# DSP1.net
KiCad netlist of a schematic drawn in Altium Designer
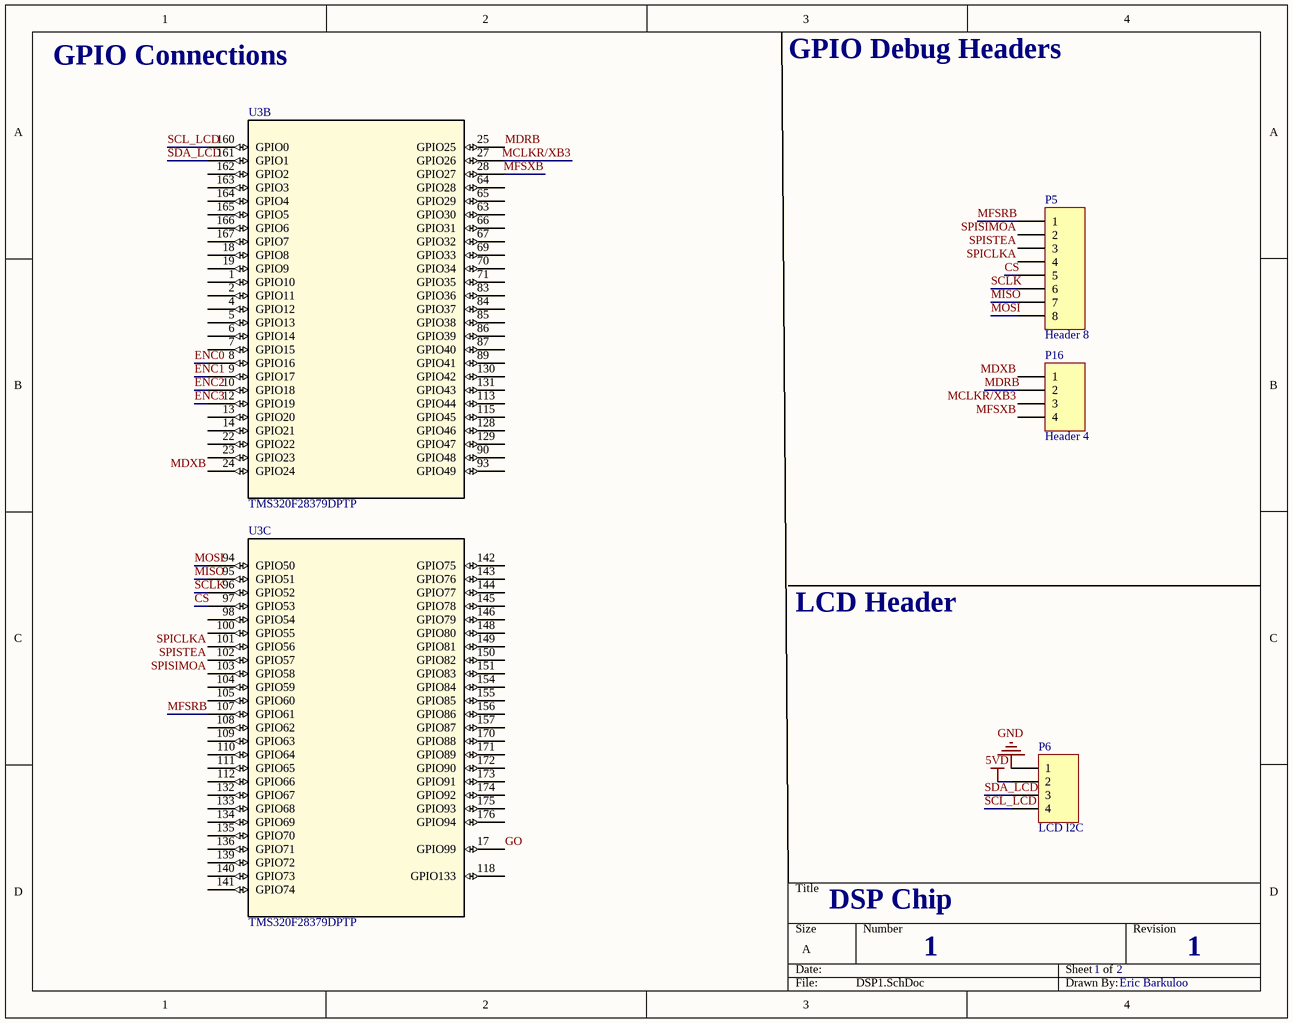
[diagram p0: DSP1.SchDoc]

(export (version "E")
  (design (tool "Eeschema 10.0.6"))
  (components
    (comp (ref "P5")
      (value "Header 8")
      (footprint "HDR1X8")
      (description "Header, 8-Pin")
      (fields (field (name "PUBLISHER") "Altium Limited"))
      (libsource (lib "Miscellaneous Connectors") (part "Header 8"))
    )
    (comp (ref "P6")
      (value "LCD I2C")
      (footprint "HDR1X4")
      (description "Header, 4-Pin")
      (fields (field (name "PUBLISHER") "Altium Limited"))
      (libsource (lib "Miscellaneous Connectors") (part "Header 4"))
    )
    (comp (ref "P16")
      (value "Header 4")
      (footprint "HDR1X4")
      (description "Header, 4-Pin")
      (fields (field (name "PUBLISHER") "Altium Limited"))
      (libsource (lib "Miscellaneous Connectors") (part "Header 4"))
    )
    (comp (ref "U3")
      (value "TMS320F28379DPTP")
      (footprint "PTP0176F_N")
      (description "Imported")
      (fields
        (field (name "PARTNUMBER") "TMS320F28379DPTPS")
        (field (name "MANUFACTURER") "Texas Instruments")
      )
      (libsource (lib "TMS320F28379DPTPT") (part "TMS320F28379DPTP"))
    )
  )
  (nets
    (net (code "1") (name "/CS") (class "Default")
      (node (ref "P5") (pin "5") (pinfunction "5_5") (pintype "passive"))
      (node (ref "U3") (pin "97") (pinfunction "GPIO53_97") (pintype "bidirectional"))
    )
    (net (code "2") (name "/ENC0") (class "Default")
      (node (ref "U3") (pin "8") (pinfunction "GPIO16_8") (pintype "bidirectional"))
    )
    (net (code "3") (name "/ENC1") (class "Default")
      (node (ref "U3") (pin "9") (pinfunction "GPIO17_9") (pintype "bidirectional"))
    )
    (net (code "4") (name "/ENC2") (class "Default")
      (node (ref "U3") (pin "10") (pinfunction "GPIO18_10") (pintype "bidirectional"))
    )
    (net (code "5") (name "/ENC3") (class "Default")
      (node (ref "U3") (pin "12") (pinfunction "GPIO19_12") (pintype "bidirectional"))
    )
    (net (code "6") (name "/GO") (class "Default")
      (node (ref "U3") (pin "17") (pinfunction "GPIO99_17") (pintype "bidirectional"))
    )
    (net (code "7") (name "/MCLKR{slash}XB3") (class "Default")
      (node (ref "P16") (pin "3") (pinfunction "3_3") (pintype "passive"))
      (node (ref "U3") (pin "27") (pinfunction "GPIO26_27") (pintype "bidirectional"))
    )
    (net (code "8") (name "/MDRB") (class "Default")
      (node (ref "P16") (pin "2") (pinfunction "2_2") (pintype "passive"))
      (node (ref "U3") (pin "25") (pinfunction "GPIO25_25") (pintype "bidirectional"))
    )
    (net (code "9") (name "/MDXB") (class "Default")
      (node (ref "P16") (pin "1") (pinfunction "1_1") (pintype "passive"))
      (node (ref "U3") (pin "24") (pinfunction "GPIO24_24") (pintype "bidirectional"))
    )
    (net (code "10") (name "/MFSRB") (class "Default")
      (node (ref "P5") (pin "1") (pinfunction "1_1") (pintype "passive"))
      (node (ref "U3") (pin "107") (pinfunction "GPIO61_107") (pintype "bidirectional"))
    )
    (net (code "11") (name "/MFSXB") (class "Default")
      (node (ref "P16") (pin "4") (pinfunction "4_4") (pintype "passive"))
      (node (ref "U3") (pin "28") (pinfunction "GPIO27_28") (pintype "bidirectional"))
    )
    (net (code "12") (name "/MISO") (class "Default")
      (node (ref "P5") (pin "7") (pinfunction "7_7") (pintype "passive"))
      (node (ref "U3") (pin "95") (pinfunction "GPIO51_95") (pintype "bidirectional"))
    )
    (net (code "13") (name "/MOSI") (class "Default")
      (node (ref "P5") (pin "8") (pinfunction "8_8") (pintype "passive"))
      (node (ref "U3") (pin "94") (pinfunction "GPIO50_94") (pintype "bidirectional"))
    )
    (net (code "14") (name "/SCLK") (class "Default")
      (node (ref "P5") (pin "6") (pinfunction "6_6") (pintype "passive"))
      (node (ref "U3") (pin "96") (pinfunction "GPIO52_96") (pintype "bidirectional"))
    )
    (net (code "15") (name "/SCL_LCD") (class "Default")
      (node (ref "P6") (pin "4") (pinfunction "4_4") (pintype "passive"))
      (node (ref "U3") (pin "160") (pinfunction "GPIO0_160") (pintype "bidirectional"))
    )
    (net (code "16") (name "/SDA_LCD") (class "Default")
      (node (ref "P6") (pin "3") (pinfunction "3_3") (pintype "passive"))
      (node (ref "U3") (pin "161") (pinfunction "GPIO1_161") (pintype "bidirectional"))
    )
    (net (code "17") (name "/SPICLKA") (class "Default")
      (node (ref "P5") (pin "4") (pinfunction "4_4") (pintype "passive"))
      (node (ref "U3") (pin "101") (pinfunction "GPIO56_101") (pintype "bidirectional"))
    )
    (net (code "18") (name "/SPISIMOA") (class "Default")
      (node (ref "P5") (pin "2") (pinfunction "2_2") (pintype "passive"))
      (node (ref "U3") (pin "103") (pinfunction "GPIO58_103") (pintype "bidirectional"))
    )
    (net (code "19") (name "/SPISTEA") (class "Default")
      (node (ref "P5") (pin "3") (pinfunction "3_3") (pintype "passive"))
      (node (ref "U3") (pin "102") (pinfunction "GPIO57_102") (pintype "bidirectional"))
    )
    (net (code "20") (name "5VD") (class "Default")
      (node (ref "P6") (pin "2") (pinfunction "2_2") (pintype "passive"))
    )
    (net (code "21") (name "GND") (class "Default")
      (node (ref "P6") (pin "1") (pinfunction "1_1") (pintype "passive"))
    )
    (net (code "22") (name "unconnected-(U3B-GPIO2-Pad162)") (class "Default")
      (node (ref "U3") (pin "162") (pinfunction "GPIO2_162") (pintype "bidirectional"))
    )
    (net (code "23") (name "unconnected-(U3B-GPIO3-Pad163)") (class "Default")
      (node (ref "U3") (pin "163") (pinfunction "GPIO3_163") (pintype "bidirectional"))
    )
    (net (code "24") (name "unconnected-(U3B-GPIO4-Pad164)") (class "Default")
      (node (ref "U3") (pin "164") (pinfunction "GPIO4_164") (pintype "bidirectional"))
    )
    (net (code "25") (name "unconnected-(U3B-GPIO5-Pad165)") (class "Default")
      (node (ref "U3") (pin "165") (pinfunction "GPIO5_165") (pintype "bidirectional"))
    )
    (net (code "26") (name "unconnected-(U3B-GPIO6-Pad166)") (class "Default")
      (node (ref "U3") (pin "166") (pinfunction "GPIO6_166") (pintype "bidirectional"))
    )
    (net (code "27") (name "unconnected-(U3B-GPIO7-Pad167)") (class "Default")
      (node (ref "U3") (pin "167") (pinfunction "GPIO7_167") (pintype "bidirectional"))
    )
    (net (code "28") (name "unconnected-(U3B-GPIO8-Pad18)") (class "Default")
      (node (ref "U3") (pin "18") (pinfunction "GPIO8_18") (pintype "bidirectional"))
    )
    (net (code "29") (name "unconnected-(U3B-GPIO9-Pad19)") (class "Default")
      (node (ref "U3") (pin "19") (pinfunction "GPIO9_19") (pintype "bidirectional"))
    )
    (net (code "30") (name "unconnected-(U3B-GPIO10-Pad1)") (class "Default")
      (node (ref "U3") (pin "1") (pinfunction "GPIO10_1") (pintype "bidirectional"))
    )
    (net (code "31") (name "unconnected-(U3B-GPIO11-Pad2)") (class "Default")
      (node (ref "U3") (pin "2") (pinfunction "GPIO11_2") (pintype "bidirectional"))
    )
    (net (code "32") (name "unconnected-(U3B-GPIO12-Pad4)") (class "Default")
      (node (ref "U3") (pin "4") (pinfunction "GPIO12_4") (pintype "bidirectional"))
    )
    (net (code "33") (name "unconnected-(U3B-GPIO13-Pad5)") (class "Default")
      (node (ref "U3") (pin "5") (pinfunction "GPIO13_5") (pintype "bidirectional"))
    )
    (net (code "34") (name "unconnected-(U3B-GPIO14-Pad6)") (class "Default")
      (node (ref "U3") (pin "6") (pinfunction "GPIO14_6") (pintype "bidirectional"))
    )
    (net (code "35") (name "unconnected-(U3B-GPIO15-Pad7)") (class "Default")
      (node (ref "U3") (pin "7") (pinfunction "GPIO15_7") (pintype "bidirectional"))
    )
    (net (code "36") (name "unconnected-(U3B-GPIO20-Pad13)") (class "Default")
      (node (ref "U3") (pin "13") (pinfunction "GPIO20_13") (pintype "bidirectional"))
    )
    (net (code "37") (name "unconnected-(U3B-GPIO21-Pad14)") (class "Default")
      (node (ref "U3") (pin "14") (pinfunction "GPIO21_14") (pintype "bidirectional"))
    )
    (net (code "38") (name "unconnected-(U3B-GPIO22-Pad22)") (class "Default")
      (node (ref "U3") (pin "22") (pinfunction "GPIO22_22") (pintype "bidirectional"))
    )
    (net (code "39") (name "unconnected-(U3B-GPIO23-Pad23)") (class "Default")
      (node (ref "U3") (pin "23") (pinfunction "GPIO23_23") (pintype "bidirectional"))
    )
    (net (code "40") (name "unconnected-(U3B-GPIO28-Pad64)") (class "Default")
      (node (ref "U3") (pin "64") (pinfunction "GPIO28_64") (pintype "bidirectional"))
    )
    (net (code "41") (name "unconnected-(U3B-GPIO29-Pad65)") (class "Default")
      (node (ref "U3") (pin "65") (pinfunction "GPIO29_65") (pintype "bidirectional"))
    )
    (net (code "42") (name "unconnected-(U3B-GPIO30-Pad63)") (class "Default")
      (node (ref "U3") (pin "63") (pinfunction "GPIO30_63") (pintype "bidirectional"))
    )
    (net (code "43") (name "unconnected-(U3B-GPIO31-Pad66)") (class "Default")
      (node (ref "U3") (pin "66") (pinfunction "GPIO31_66") (pintype "bidirectional"))
    )
    (net (code "44") (name "unconnected-(U3B-GPIO32-Pad67)") (class "Default")
      (node (ref "U3") (pin "67") (pinfunction "GPIO32_67") (pintype "bidirectional"))
    )
    (net (code "45") (name "unconnected-(U3B-GPIO33-Pad69)") (class "Default")
      (node (ref "U3") (pin "69") (pinfunction "GPIO33_69") (pintype "bidirectional"))
    )
    (net (code "46") (name "unconnected-(U3B-GPIO34-Pad70)") (class "Default")
      (node (ref "U3") (pin "70") (pinfunction "GPIO34_70") (pintype "bidirectional"))
    )
    (net (code "47") (name "unconnected-(U3B-GPIO35-Pad71)") (class "Default")
      (node (ref "U3") (pin "71") (pinfunction "GPIO35_71") (pintype "bidirectional"))
    )
    (net (code "48") (name "unconnected-(U3B-GPIO36-Pad83)") (class "Default")
      (node (ref "U3") (pin "83") (pinfunction "GPIO36_83") (pintype "bidirectional"))
    )
    (net (code "49") (name "unconnected-(U3B-GPIO37-Pad84)") (class "Default")
      (node (ref "U3") (pin "84") (pinfunction "GPIO37_84") (pintype "bidirectional"))
    )
    (net (code "50") (name "unconnected-(U3B-GPIO38-Pad85)") (class "Default")
      (node (ref "U3") (pin "85") (pinfunction "GPIO38_85") (pintype "bidirectional"))
    )
    (net (code "51") (name "unconnected-(U3B-GPIO39-Pad86)") (class "Default")
      (node (ref "U3") (pin "86") (pinfunction "GPIO39_86") (pintype "bidirectional"))
    )
    (net (code "52") (name "unconnected-(U3B-GPIO40-Pad87)") (class "Default")
      (node (ref "U3") (pin "87") (pinfunction "GPIO40_87") (pintype "bidirectional"))
    )
    (net (code "53") (name "unconnected-(U3B-GPIO41-Pad89)") (class "Default")
      (node (ref "U3") (pin "89") (pinfunction "GPIO41_89") (pintype "bidirectional"))
    )
    (net (code "54") (name "unconnected-(U3B-GPIO42-Pad130)") (class "Default")
      (node (ref "U3") (pin "130") (pinfunction "GPIO42_130") (pintype "bidirectional"))
    )
    (net (code "55") (name "unconnected-(U3B-GPIO43-Pad131)") (class "Default")
      (node (ref "U3") (pin "131") (pinfunction "GPIO43_131") (pintype "bidirectional"))
    )
    (net (code "56") (name "unconnected-(U3B-GPIO44-Pad113)") (class "Default")
      (node (ref "U3") (pin "113") (pinfunction "GPIO44_113") (pintype "bidirectional"))
    )
    (net (code "57") (name "unconnected-(U3B-GPIO45-Pad115)") (class "Default")
      (node (ref "U3") (pin "115") (pinfunction "GPIO45_115") (pintype "bidirectional"))
    )
    (net (code "58") (name "unconnected-(U3B-GPIO46-Pad128)") (class "Default")
      (node (ref "U3") (pin "128") (pinfunction "GPIO46_128") (pintype "bidirectional"))
    )
    (net (code "59") (name "unconnected-(U3B-GPIO47-Pad129)") (class "Default")
      (node (ref "U3") (pin "129") (pinfunction "GPIO47_129") (pintype "bidirectional"))
    )
    (net (code "60") (name "unconnected-(U3B-GPIO48-Pad90)") (class "Default")
      (node (ref "U3") (pin "90") (pinfunction "GPIO48_90") (pintype "bidirectional"))
    )
    (net (code "61") (name "unconnected-(U3B-GPIO49-Pad93)") (class "Default")
      (node (ref "U3") (pin "93") (pinfunction "GPIO49_93") (pintype "bidirectional"))
    )
    (net (code "62") (name "unconnected-(U3C-GPIO54-Pad98)") (class "Default")
      (node (ref "U3") (pin "98") (pinfunction "GPIO54_98") (pintype "bidirectional"))
    )
    (net (code "63") (name "unconnected-(U3C-GPIO55-Pad100)") (class "Default")
      (node (ref "U3") (pin "100") (pinfunction "GPIO55_100") (pintype "bidirectional"))
    )
    (net (code "64") (name "unconnected-(U3C-GPIO59-Pad104)") (class "Default")
      (node (ref "U3") (pin "104") (pinfunction "GPIO59_104") (pintype "bidirectional"))
    )
    (net (code "65") (name "unconnected-(U3C-GPIO60-Pad105)") (class "Default")
      (node (ref "U3") (pin "105") (pinfunction "GPIO60_105") (pintype "bidirectional"))
    )
    (net (code "66") (name "unconnected-(U3C-GPIO62-Pad108)") (class "Default")
      (node (ref "U3") (pin "108") (pinfunction "GPIO62_108") (pintype "bidirectional"))
    )
    (net (code "67") (name "unconnected-(U3C-GPIO63-Pad109)") (class "Default")
      (node (ref "U3") (pin "109") (pinfunction "GPIO63_109") (pintype "bidirectional"))
    )
    (net (code "68") (name "unconnected-(U3C-GPIO64-Pad110)") (class "Default")
      (node (ref "U3") (pin "110") (pinfunction "GPIO64_110") (pintype "bidirectional"))
    )
    (net (code "69") (name "unconnected-(U3C-GPIO65-Pad111)") (class "Default")
      (node (ref "U3") (pin "111") (pinfunction "GPIO65_111") (pintype "bidirectional"))
    )
    (net (code "70") (name "unconnected-(U3C-GPIO66-Pad112)") (class "Default")
      (node (ref "U3") (pin "112") (pinfunction "GPIO66_112") (pintype "bidirectional"))
    )
    (net (code "71") (name "unconnected-(U3C-GPIO67-Pad132)") (class "Default")
      (node (ref "U3") (pin "132") (pinfunction "GPIO67_132") (pintype "bidirectional"))
    )
    (net (code "72") (name "unconnected-(U3C-GPIO68-Pad133)") (class "Default")
      (node (ref "U3") (pin "133") (pinfunction "GPIO68_133") (pintype "bidirectional"))
    )
    (net (code "73") (name "unconnected-(U3C-GPIO69-Pad134)") (class "Default")
      (node (ref "U3") (pin "134") (pinfunction "GPIO69_134") (pintype "bidirectional"))
    )
    (net (code "74") (name "unconnected-(U3C-GPIO70-Pad135)") (class "Default")
      (node (ref "U3") (pin "135") (pinfunction "GPIO70_135") (pintype "bidirectional"))
    )
    (net (code "75") (name "unconnected-(U3C-GPIO71-Pad136)") (class "Default")
      (node (ref "U3") (pin "136") (pinfunction "GPIO71_136") (pintype "bidirectional"))
    )
    (net (code "76") (name "unconnected-(U3C-GPIO72-Pad139)") (class "Default")
      (node (ref "U3") (pin "139") (pinfunction "GPIO72_139") (pintype "bidirectional"))
    )
    (net (code "77") (name "unconnected-(U3C-GPIO73-Pad140)") (class "Default")
      (node (ref "U3") (pin "140") (pinfunction "GPIO73_140") (pintype "bidirectional"))
    )
    (net (code "78") (name "unconnected-(U3C-GPIO74-Pad141)") (class "Default")
      (node (ref "U3") (pin "141") (pinfunction "GPIO74_141") (pintype "bidirectional"))
    )
    (net (code "79") (name "unconnected-(U3C-GPIO75-Pad142)") (class "Default")
      (node (ref "U3") (pin "142") (pinfunction "GPIO75_142") (pintype "bidirectional"))
    )
    (net (code "80") (name "unconnected-(U3C-GPIO76-Pad143)") (class "Default")
      (node (ref "U3") (pin "143") (pinfunction "GPIO76_143") (pintype "bidirectional"))
    )
    (net (code "81") (name "unconnected-(U3C-GPIO77-Pad144)") (class "Default")
      (node (ref "U3") (pin "144") (pinfunction "GPIO77_144") (pintype "bidirectional"))
    )
    (net (code "82") (name "unconnected-(U3C-GPIO78-Pad145)") (class "Default")
      (node (ref "U3") (pin "145") (pinfunction "GPIO78_145") (pintype "bidirectional"))
    )
    (net (code "83") (name "unconnected-(U3C-GPIO79-Pad146)") (class "Default")
      (node (ref "U3") (pin "146") (pinfunction "GPIO79_146") (pintype "bidirectional"))
    )
    (net (code "84") (name "unconnected-(U3C-GPIO80-Pad148)") (class "Default")
      (node (ref "U3") (pin "148") (pinfunction "GPIO80_148") (pintype "bidirectional"))
    )
    (net (code "85") (name "unconnected-(U3C-GPIO81-Pad149)") (class "Default")
      (node (ref "U3") (pin "149") (pinfunction "GPIO81_149") (pintype "bidirectional"))
    )
    (net (code "86") (name "unconnected-(U3C-GPIO82-Pad150)") (class "Default")
      (node (ref "U3") (pin "150") (pinfunction "GPIO82_150") (pintype "bidirectional"))
    )
    (net (code "87") (name "unconnected-(U3C-GPIO83-Pad151)") (class "Default")
      (node (ref "U3") (pin "151") (pinfunction "GPIO83_151") (pintype "bidirectional"))
    )
    (net (code "88") (name "unconnected-(U3C-GPIO84-Pad154)") (class "Default")
      (node (ref "U3") (pin "154") (pinfunction "GPIO84_154") (pintype "bidirectional"))
    )
    (net (code "89") (name "unconnected-(U3C-GPIO85-Pad155)") (class "Default")
      (node (ref "U3") (pin "155") (pinfunction "GPIO85_155") (pintype "bidirectional"))
    )
    (net (code "90") (name "unconnected-(U3C-GPIO86-Pad156)") (class "Default")
      (node (ref "U3") (pin "156") (pinfunction "GPIO86_156") (pintype "bidirectional"))
    )
    (net (code "91") (name "unconnected-(U3C-GPIO87-Pad157)") (class "Default")
      (node (ref "U3") (pin "157") (pinfunction "GPIO87_157") (pintype "bidirectional"))
    )
    (net (code "92") (name "unconnected-(U3C-GPIO88-Pad170)") (class "Default")
      (node (ref "U3") (pin "170") (pinfunction "GPIO88_170") (pintype "bidirectional"))
    )
    (net (code "93") (name "unconnected-(U3C-GPIO89-Pad171)") (class "Default")
      (node (ref "U3") (pin "171") (pinfunction "GPIO89_171") (pintype "bidirectional"))
    )
    (net (code "94") (name "unconnected-(U3C-GPIO90-Pad172)") (class "Default")
      (node (ref "U3") (pin "172") (pinfunction "GPIO90_172") (pintype "bidirectional"))
    )
    (net (code "95") (name "unconnected-(U3C-GPIO91-Pad173)") (class "Default")
      (node (ref "U3") (pin "173") (pinfunction "GPIO91_173") (pintype "bidirectional"))
    )
    (net (code "96") (name "unconnected-(U3C-GPIO92-Pad174)") (class "Default")
      (node (ref "U3") (pin "174") (pinfunction "GPIO92_174") (pintype "bidirectional"))
    )
    (net (code "97") (name "unconnected-(U3C-GPIO93-Pad175)") (class "Default")
      (node (ref "U3") (pin "175") (pinfunction "GPIO93_175") (pintype "bidirectional"))
    )
    (net (code "98") (name "unconnected-(U3C-GPIO94-Pad176)") (class "Default")
      (node (ref "U3") (pin "176") (pinfunction "GPIO94_176") (pintype "bidirectional"))
    )
    (net (code "99") (name "unconnected-(U3C-GPIO133-Pad118)") (class "Default")
      (node (ref "U3") (pin "118") (pinfunction "GPIO133_118") (pintype "bidirectional"))
    )
  )
)
